# design.net
KiCad netlist of a schematic drawn in EasyEDA Pro
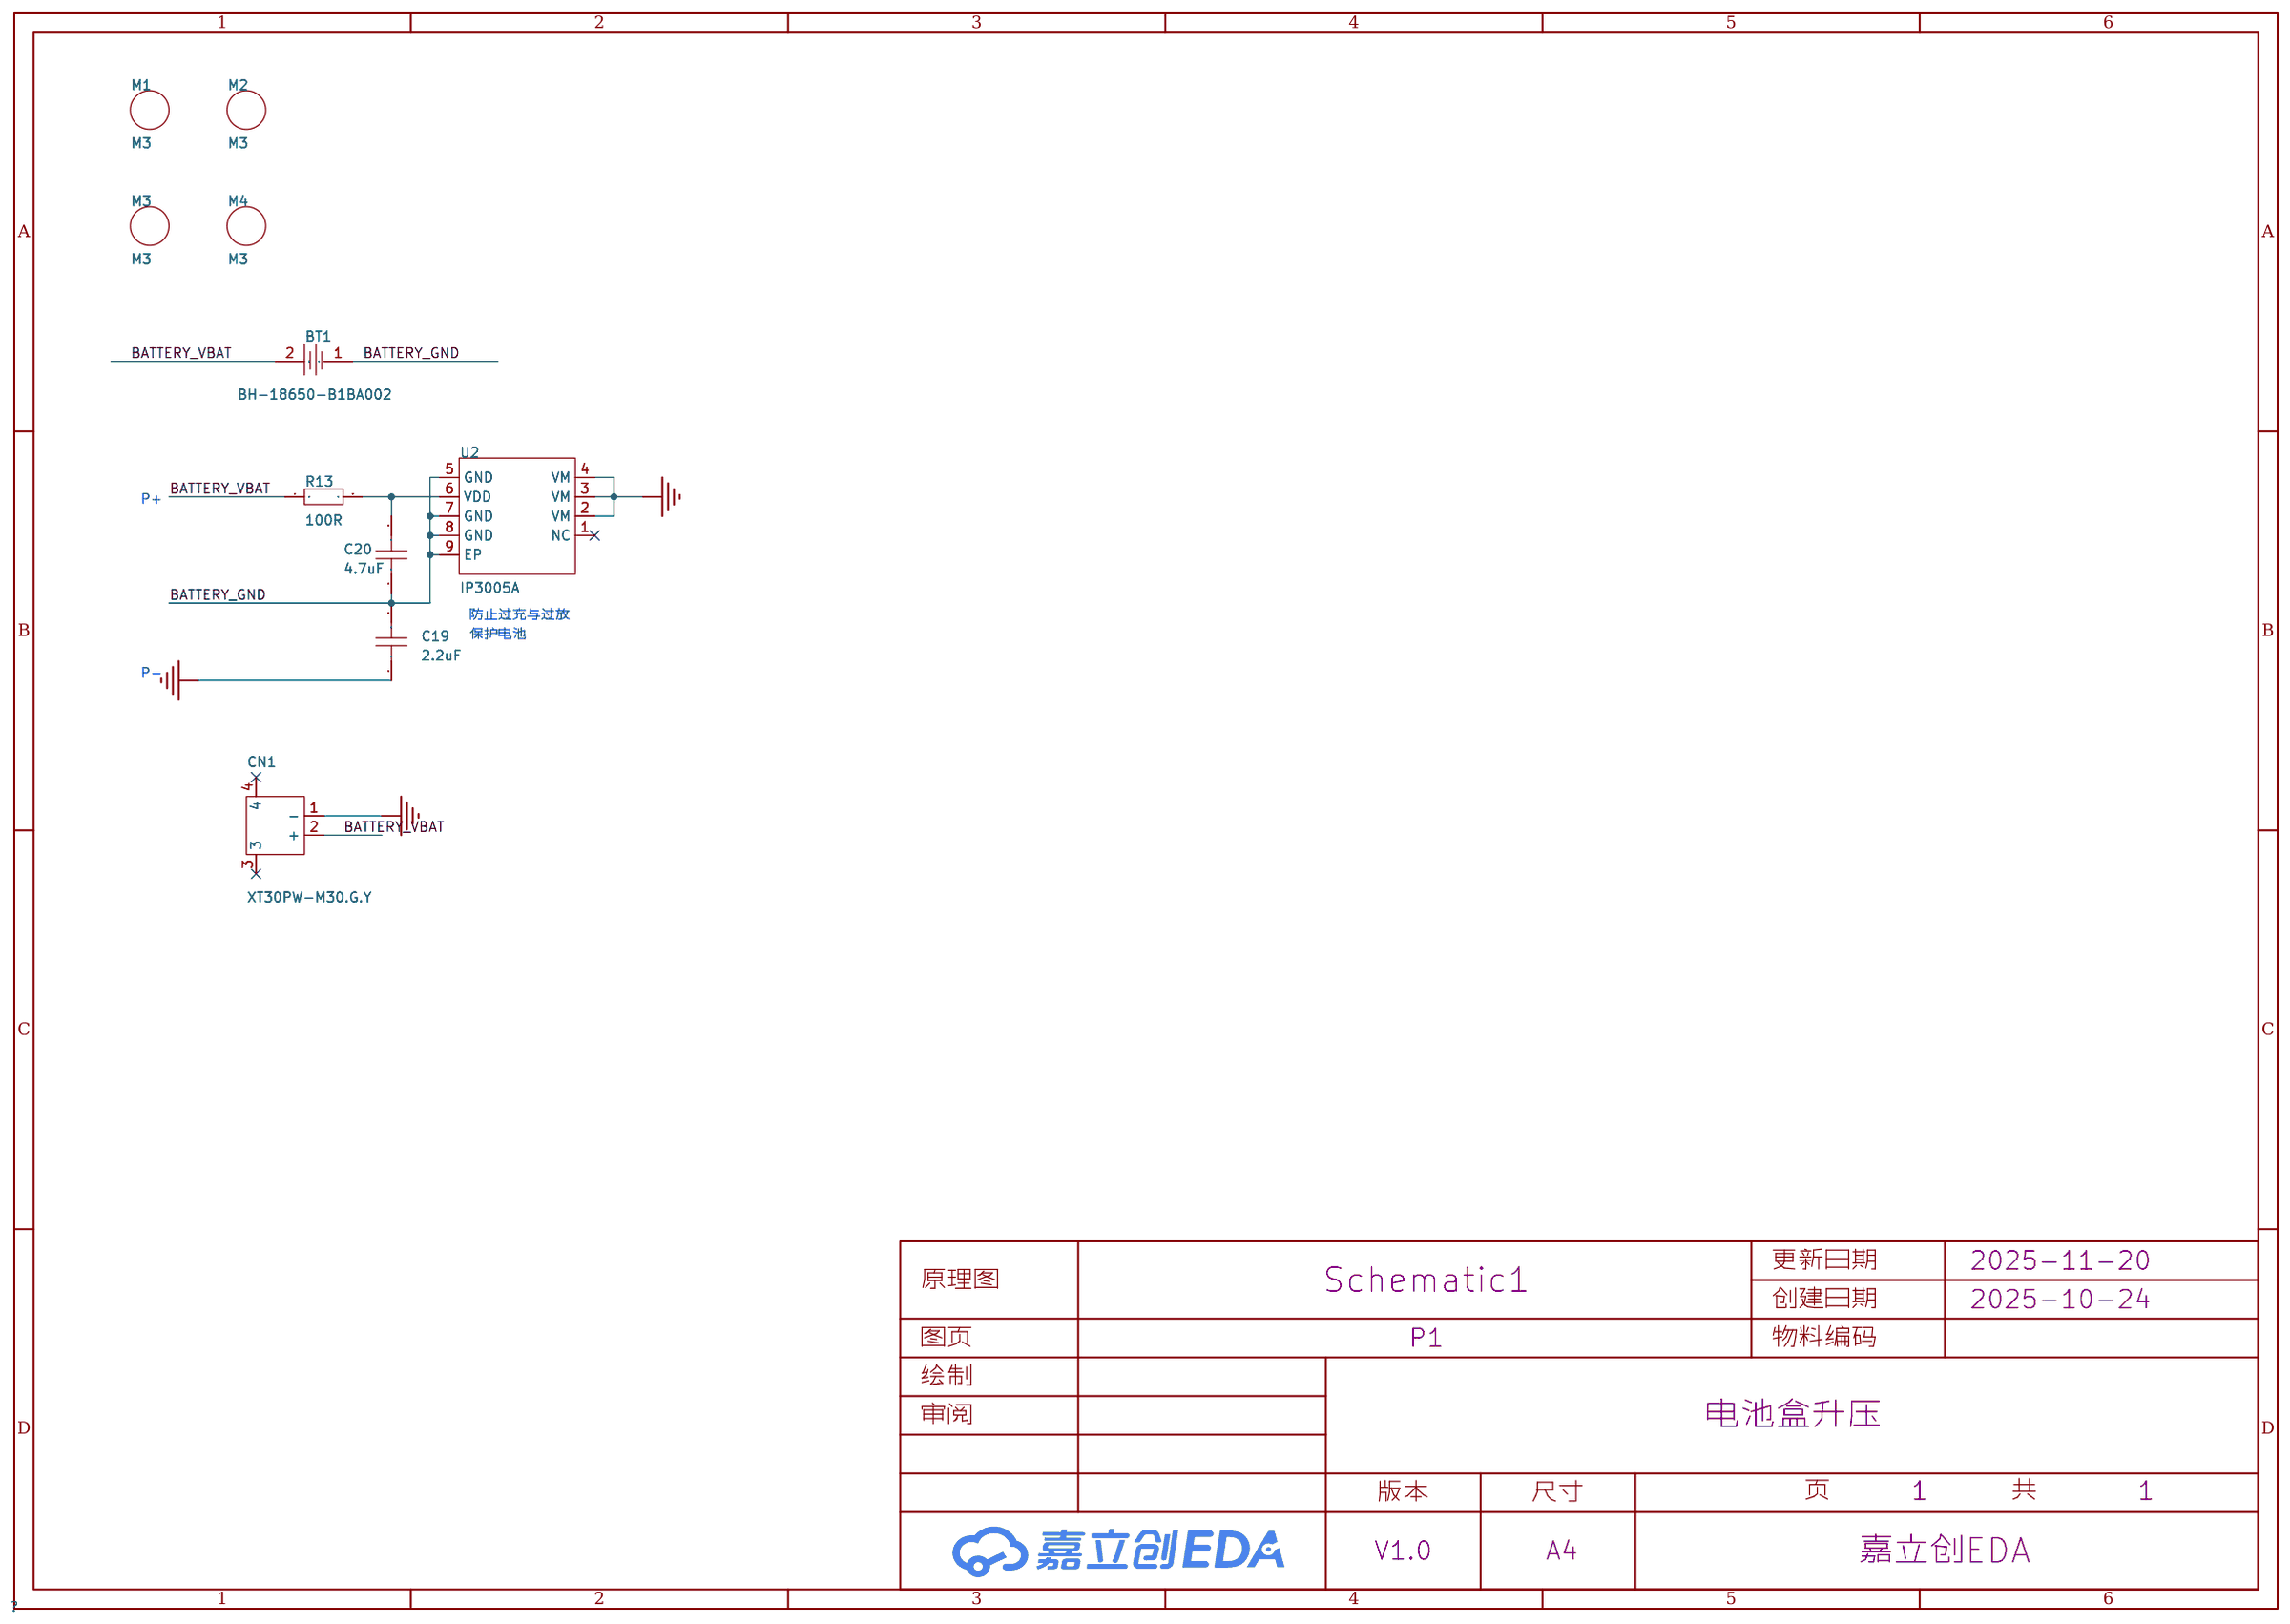
[diagram p0: schematic sheet]

(export (version "E")
  (design (tool "Eeschema 10.0.6"))
  (components
    (comp (ref "BT1")
      (value "BH-18650-B1BA002")
      (footprint "easyedapro:BATTERY-SMD_18650-1S-L77.1-W20.7-1")
      (description "连接器类型:电池盒;适用电池规格:18650;")
      (fields (field (name "Manufacturer") "MYOUNG(美阳)"))
      (libsource (lib "easyedapro") (part "BH-18650-B1BA002"))
    )
    (comp (ref "C19")
      (value "2.2uF")
      (footprint "easyedapro:C0603")
      (description "容值:2.2uF;精度:±20%;额定电压:10V;温度系数:X5R;")
      (fields (field (name "Manufacturer Part") "0603X225M100NT") (field (name "Manufacturer") "FH(风华)"))
      (libsource (lib "easyedapro") (part "0603X225M100NT"))
    )
    (comp (ref "C20")
      (value "4.7uF")
      (footprint "easyedapro:C0603")
      (description "容值:4.7uF;精度:±10%;额定电压:25V;温度系数:X6S;")
      (fields
        (field (name "Manufacturer Part") "GRT188C81E475KE13D")
        (field (name "Manufacturer") "muRata(村田)")
      )
      (libsource (lib "easyedapro") (part "GRT188C81E475KE13D"))
    )
    (comp (ref "CN1")
      (value "XT30PW-M30.G.Y")
      (footprint "easyedapro:CONN-TH_XT30PW-M")
      (description "类别:-;类型1:-;")
      (fields (field (name "Manufacturer") "AMASS(艾迈斯)"))
      (libsource (lib "easyedapro") (part "XT30PW-M"))
    )
    (comp (ref "M1")
      (value "M3")
      (footprint "easyedapro:M3 125X200")
      (description "铜柱孔")
      (libsource (lib "easyedapro") (part "M3"))
    )
    (comp (ref "M2")
      (value "M3")
      (footprint "easyedapro:M3 125X200")
      (description "铜柱孔")
      (libsource (lib "easyedapro") (part "M3"))
    )
    (comp (ref "M3")
      (value "M3")
      (footprint "easyedapro:M3 125X200")
      (description "铜柱孔")
      (libsource (lib "easyedapro") (part "M3"))
    )
    (comp (ref "M4")
      (value "M3")
      (footprint "easyedapro:M3 125X200")
      (description "铜柱孔")
      (libsource (lib "easyedapro") (part "M3"))
    )
    (comp (ref "R13")
      (value "100R")
      (footprint "easyedapro:R0603")
      (libsource (lib "easyedapro") (part "电阻"))
    )
    (comp (ref "U2")
      (value "IP3005A")
      (footprint "easyedapro:ESOP-8_L4.9-W3.9-P1.27-LS6.0-BL-EP")
      (description "过充电压:4.28V,过充恢复电压:4.1V,高精度内置MOSFET单节锂电池保护IC")
      (fields (field (name "Manufacturer") "INJOINIC(英集芯)"))
      (libsource (lib "easyedapro") (part "IP3005A"))
    )
  )
  (nets
    (net (code "1") (name "/BATTERY_GND") (class "Default")
      (node (ref "BT1") (pin "1") (pinfunction "1_1") (pintype "input"))
      (node (ref "C19") (pin "2") (pinfunction "2_2") (pintype "unspecified"))
      (node (ref "C20") (pin "1") (pinfunction "1_1") (pintype "unspecified"))
      (node (ref "U2") (pin "5") (pinfunction "GND_5") (pintype "unspecified"))
      (node (ref "U2") (pin "7") (pinfunction "GND_7") (pintype "unspecified"))
      (node (ref "U2") (pin "8") (pinfunction "GND_8") (pintype "unspecified"))
      (node (ref "U2") (pin "9") (pinfunction "EP_9") (pintype "unspecified"))
    )
    (net (code "2") (name "/BATTERY_VBAT") (class "Default")
      (node (ref "BT1") (pin "2") (pinfunction "2_2") (pintype "input"))
      (node (ref "CN1") (pin "2") (pinfunction "+_2") (pintype "unspecified"))
      (node (ref "R13") (pin "1") (pinfunction "1_1") (pintype "input"))
    )
    (net (code "3") (name "GND") (class "Default")
      (node (ref "C19") (pin "1") (pinfunction "1_1") (pintype "unspecified"))
      (node (ref "CN1") (pin "1") (pinfunction "-_1") (pintype "unspecified"))
      (node (ref "U2") (pin "2") (pinfunction "VM_2") (pintype "unspecified"))
      (node (ref "U2") (pin "3") (pinfunction "VM_3") (pintype "unspecified"))
      (node (ref "U2") (pin "4") (pinfunction "VM_4") (pintype "unspecified"))
    )
    (net (code "4") (name "Net-(U2-VDD)") (class "Default")
      (node (ref "C20") (pin "2") (pinfunction "2_2") (pintype "unspecified"))
      (node (ref "R13") (pin "2") (pinfunction "2_2") (pintype "input"))
      (node (ref "U2") (pin "6") (pinfunction "VDD_6") (pintype "unspecified"))
    )
    (net (code "5") (name "unconnected-(CN1-Pad3)") (class "Default")
      (node (ref "CN1") (pin "3") (pinfunction "3_3") (pintype "unspecified+no_connect"))
    )
    (net (code "6") (name "unconnected-(CN1-Pad4)") (class "Default")
      (node (ref "CN1") (pin "4") (pinfunction "4_4") (pintype "unspecified+no_connect"))
    )
    (net (code "7") (name "unconnected-(U2-NC-Pad1)") (class "Default")
      (node (ref "U2") (pin "1") (pinfunction "NC_1") (pintype "unspecified+no_connect"))
    )
  )
)
